# CON_PCIe_X4.net
KiCad netlist of a schematic drawn in Altium Designer
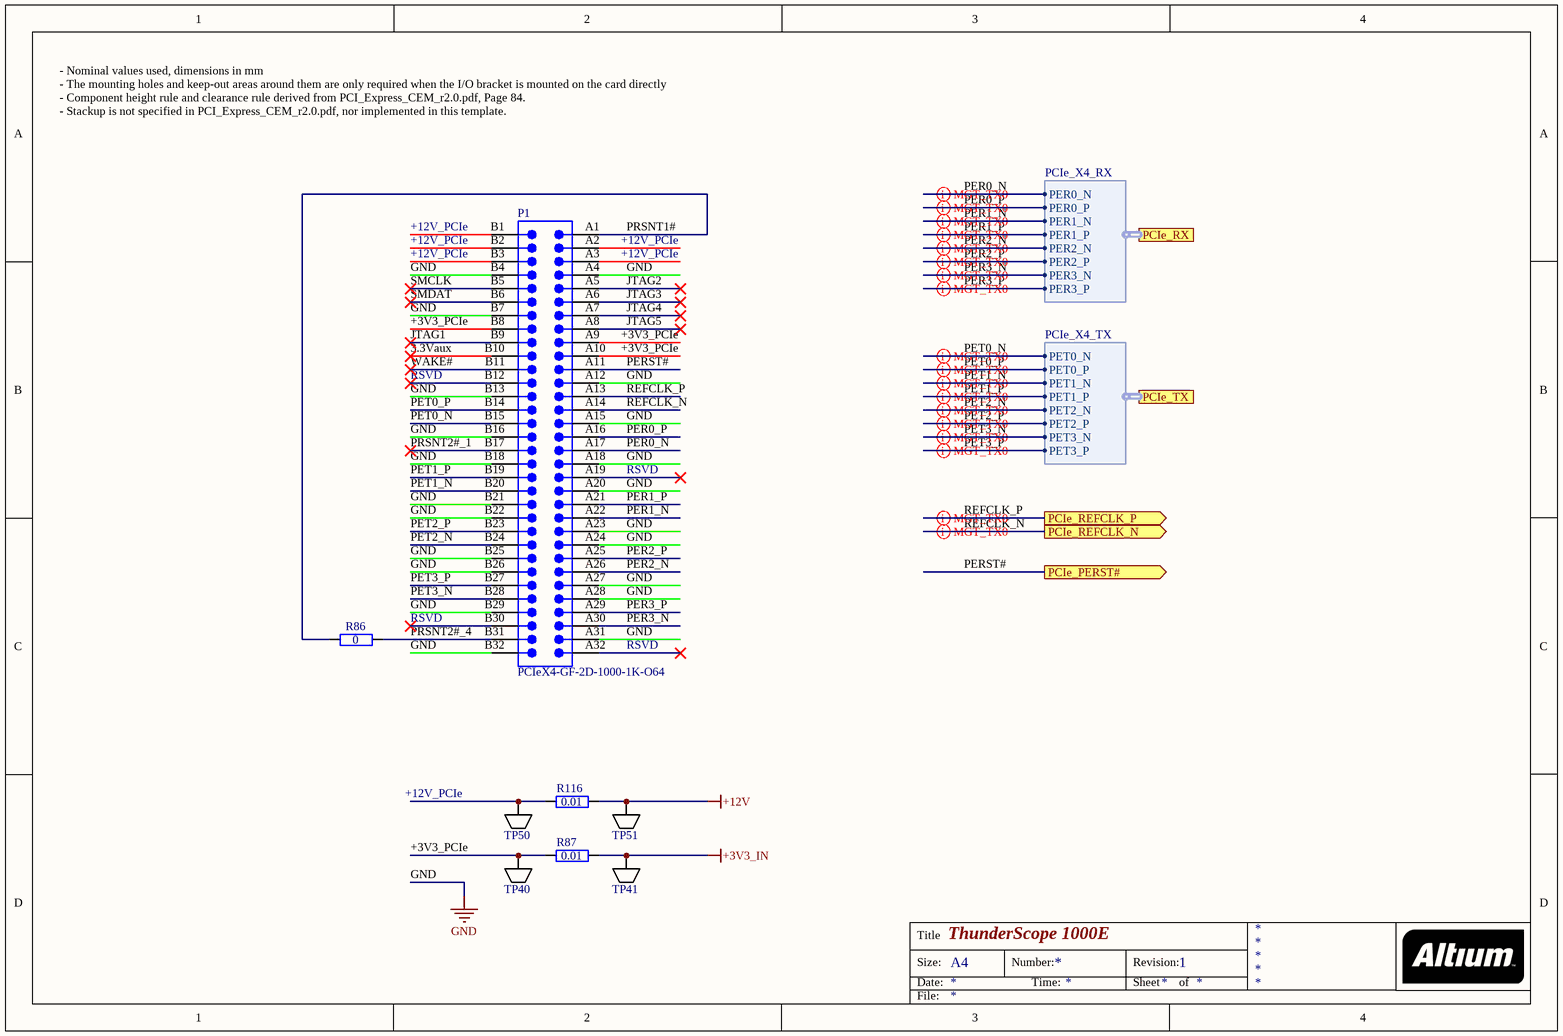
[diagram p0: CON_PCIe_X4.SchDoc]

(export (version "E")
  (design (tool "Eeschema 10.0.6"))
  (components
    (comp (ref "P1")
      (value "PCIeX4-GF-2D-1000-1K-O64")
      (footprint "PCIeX4-GF-2D-1000-1K-O64")
      (description "Golden finger, PCIeX4, Dual, Opposite, Pitch 1mm, 64-Position")
      (fields (field (name "PUBLISHER") "Altium"))
      (libsource (lib "Altium Content Vault") (part "PCIeX4-GF-2D-1000-1K-O64"))
    )
    (comp (ref "R86")
      (value "0")
      (footprint "GEN_R_0402")
      (libsource (lib "DSO") (part "RES 0 OHM 1/16W 0402"))
    )
    (comp (ref "R87")
      (value "0.01")
      (footprint "GEN_R_0603")
      (fields (field (name "TOLERANCE") "1%"))
      (libsource (lib "DSO") (part "RES 0.01 OHM 1% 1/4W 0603"))
    )
    (comp (ref "R116")
      (value "0.01")
      (footprint "GEN_R_0603")
      (fields (field (name "TOLERANCE") "1%"))
      (libsource (lib "DSO") (part "RES 0.01 OHM 1% 1/4W 0603"))
    )
    (comp (ref "TP40")
      (value "5015")
      (footprint "KEY_5015")
      (libsource (lib "DSO") (part "TP KEYSTONE 5015"))
    )
    (comp (ref "TP41")
      (value "5015")
      (footprint "KEY_5015")
      (libsource (lib "DSO") (part "TP KEYSTONE 5015"))
    )
    (comp (ref "TP50")
      (value "5015")
      (footprint "KEY_5015")
      (libsource (lib "DSO") (part "TP KEYSTONE 5015"))
    )
    (comp (ref "TP51")
      (value "5015")
      (footprint "KEY_5015")
      (libsource (lib "DSO") (part "TP KEYSTONE 5015"))
    )
  )
  (nets
    (net (code "3") (name "+3V3_IN") (class "Default")
      (node (ref "R87") (pin "2") (pinfunction "2_2") (pintype "passive"))
      (node (ref "TP41") (pin "1") (pinfunction "1_1") (pintype "passive"))
    )
    (net (code "4") (name "+12V") (class "Default")
      (node (ref "R116") (pin "2") (pinfunction "2_2") (pintype "passive"))
      (node (ref "TP51") (pin "1") (pinfunction "1_1") (pintype "passive"))
    )
    (net (code "5") (name "/+3V3_PCIe") (class "Default")
      (node (ref "P1") (pin "A10") (pinfunction "A10_A10") (pintype "passive"))
      (node (ref "P1") (pin "A9") (pinfunction "A9_A9") (pintype "passive"))
      (node (ref "P1") (pin "B8") (pinfunction "B8_B8") (pintype "passive"))
      (node (ref "R87") (pin "1") (pinfunction "1_1") (pintype "passive"))
      (node (ref "TP40") (pin "1") (pinfunction "1_1") (pintype "passive"))
    )
    (net (code "6") (name "/+12V_PCIe") (class "Default")
      (node (ref "P1") (pin "A2") (pinfunction "A2_A2") (pintype "passive"))
      (node (ref "P1") (pin "A3") (pinfunction "A3_A3") (pintype "passive"))
      (node (ref "P1") (pin "B1") (pinfunction "B1_B1") (pintype "passive"))
      (node (ref "P1") (pin "B2") (pinfunction "B2_B2") (pintype "passive"))
      (node (ref "P1") (pin "B3") (pinfunction "B3_B3") (pintype "passive"))
      (node (ref "R116") (pin "1") (pinfunction "1_1") (pintype "passive"))
      (node (ref "TP50") (pin "1") (pinfunction "1_1") (pintype "passive"))
    )
    (net (code "7") (name "/3.3Vaux") (class "Default")
      (node (ref "P1") (pin "B10") (pinfunction "B10_B10") (pintype "passive+no_connect"))
    )
    (net (code "8") (name "/JTAG1") (class "Default")
      (node (ref "P1") (pin "B9") (pinfunction "B9_B9") (pintype "passive+no_connect"))
    )
    (net (code "9") (name "/JTAG2") (class "Default")
      (node (ref "P1") (pin "A5") (pinfunction "A5_A5") (pintype "passive+no_connect"))
    )
    (net (code "10") (name "/JTAG3") (class "Default")
      (node (ref "P1") (pin "A6") (pinfunction "A6_A6") (pintype "passive+no_connect"))
    )
    (net (code "11") (name "/JTAG4") (class "Default")
      (node (ref "P1") (pin "A7") (pinfunction "A7_A7") (pintype "passive+no_connect"))
    )
    (net (code "12") (name "/JTAG5") (class "Default")
      (node (ref "P1") (pin "A8") (pinfunction "A8_A8") (pintype "passive+no_connect"))
    )
    (net (code "13") (name "/PER0_N") (class "Default")
      (node (ref "P1") (pin "A17") (pinfunction "A17_A17") (pintype "passive"))
    )
    (net (code "14") (name "/PER0_P") (class "Default")
      (node (ref "P1") (pin "A16") (pinfunction "A16_A16") (pintype "passive"))
    )
    (net (code "15") (name "/PER1_N") (class "Default")
      (node (ref "P1") (pin "A22") (pinfunction "A22_A22") (pintype "passive"))
    )
    (net (code "16") (name "/PER1_P") (class "Default")
      (node (ref "P1") (pin "A21") (pinfunction "A21_A21") (pintype "passive"))
    )
    (net (code "17") (name "/PER2_N") (class "Default")
      (node (ref "P1") (pin "A26") (pinfunction "A26_A26") (pintype "passive"))
    )
    (net (code "18") (name "/PER2_P") (class "Default")
      (node (ref "P1") (pin "A25") (pinfunction "A25_A25") (pintype "passive"))
    )
    (net (code "19") (name "/PER3_N") (class "Default")
      (node (ref "P1") (pin "A30") (pinfunction "A30_A30") (pintype "passive"))
    )
    (net (code "20") (name "/PER3_P") (class "Default")
      (node (ref "P1") (pin "A29") (pinfunction "A29_A29") (pintype "passive"))
    )
    (net (code "21") (name "/PERST#") (class "Default")
      (node (ref "P1") (pin "A11") (pinfunction "A11_A11") (pintype "passive"))
    )
    (net (code "22") (name "/PET0_N") (class "Default")
      (node (ref "P1") (pin "B15") (pinfunction "B15_B15") (pintype "passive"))
    )
    (net (code "23") (name "/PET0_P") (class "Default")
      (node (ref "P1") (pin "B14") (pinfunction "B14_B14") (pintype "passive"))
    )
    (net (code "24") (name "/PET1_N") (class "Default")
      (node (ref "P1") (pin "B20") (pinfunction "B20_B20") (pintype "passive"))
    )
    (net (code "25") (name "/PET1_P") (class "Default")
      (node (ref "P1") (pin "B19") (pinfunction "B19_B19") (pintype "passive"))
    )
    (net (code "26") (name "/PET2_N") (class "Default")
      (node (ref "P1") (pin "B24") (pinfunction "B24_B24") (pintype "passive"))
    )
    (net (code "27") (name "/PET2_P") (class "Default")
      (node (ref "P1") (pin "B23") (pinfunction "B23_B23") (pintype "passive"))
    )
    (net (code "28") (name "/PET3_N") (class "Default")
      (node (ref "P1") (pin "B28") (pinfunction "B28_B28") (pintype "passive"))
    )
    (net (code "29") (name "/PET3_P") (class "Default")
      (node (ref "P1") (pin "B27") (pinfunction "B27_B27") (pintype "passive"))
    )
    (net (code "30") (name "/PRSNT1#") (class "Default")
      (node (ref "P1") (pin "A1") (pinfunction "A1_A1") (pintype "passive"))
      (node (ref "R86") (pin "1") (pinfunction "1_1") (pintype "passive"))
    )
    (net (code "31") (name "/PRSNT2#_1") (class "Default")
      (node (ref "P1") (pin "B17") (pinfunction "B17_B17") (pintype "passive+no_connect"))
    )
    (net (code "32") (name "/PRSNT2#_4") (class "Default")
      (node (ref "P1") (pin "B31") (pinfunction "B31_B31") (pintype "passive"))
      (node (ref "R86") (pin "2") (pinfunction "2_2") (pintype "passive"))
    )
    (net (code "33") (name "/REFCLK_N") (class "Default")
      (node (ref "P1") (pin "A14") (pinfunction "A14_A14") (pintype "passive"))
    )
    (net (code "34") (name "/REFCLK_P") (class "Default")
      (node (ref "P1") (pin "A13") (pinfunction "A13_A13") (pintype "passive"))
    )
    (net (code "35") (name "/SMCLK") (class "Default")
      (node (ref "P1") (pin "B5") (pinfunction "B5_B5") (pintype "passive+no_connect"))
    )
    (net (code "36") (name "/SMDAT") (class "Default")
      (node (ref "P1") (pin "B6") (pinfunction "B6_B6") (pintype "passive+no_connect"))
    )
    (net (code "37") (name "/WAKE#") (class "Default")
      (node (ref "P1") (pin "B11") (pinfunction "B11_B11") (pintype "passive+no_connect"))
    )
    (net (code "40") (name "GND") (class "Default")
      (node (ref "P1") (pin "A12") (pinfunction "A12_A12") (pintype "passive"))
      (node (ref "P1") (pin "A15") (pinfunction "A15_A15") (pintype "passive"))
      (node (ref "P1") (pin "A18") (pinfunction "A18_A18") (pintype "passive"))
      (node (ref "P1") (pin "A20") (pinfunction "A20_A20") (pintype "passive"))
      (node (ref "P1") (pin "A23") (pinfunction "A23_A23") (pintype "passive"))
      (node (ref "P1") (pin "A24") (pinfunction "A24_A24") (pintype "passive"))
      (node (ref "P1") (pin "A27") (pinfunction "A27_A27") (pintype "passive"))
      (node (ref "P1") (pin "A28") (pinfunction "A28_A28") (pintype "passive"))
      (node (ref "P1") (pin "A31") (pinfunction "A31_A31") (pintype "passive"))
      (node (ref "P1") (pin "A4") (pinfunction "A4_A4") (pintype "passive"))
      (node (ref "P1") (pin "B13") (pinfunction "B13_B13") (pintype "passive"))
      (node (ref "P1") (pin "B16") (pinfunction "B16_B16") (pintype "passive"))
      (node (ref "P1") (pin "B18") (pinfunction "B18_B18") (pintype "passive"))
      (node (ref "P1") (pin "B21") (pinfunction "B21_B21") (pintype "passive"))
      (node (ref "P1") (pin "B22") (pinfunction "B22_B22") (pintype "passive"))
      (node (ref "P1") (pin "B25") (pinfunction "B25_B25") (pintype "passive"))
      (node (ref "P1") (pin "B26") (pinfunction "B26_B26") (pintype "passive"))
      (node (ref "P1") (pin "B29") (pinfunction "B29_B29") (pintype "passive"))
      (node (ref "P1") (pin "B32") (pinfunction "B32_B32") (pintype "passive"))
      (node (ref "P1") (pin "B4") (pinfunction "B4_B4") (pintype "passive"))
      (node (ref "P1") (pin "B7") (pinfunction "B7_B7") (pintype "passive"))
    )
    (net (code "41") (name "unconnected-(P1-PadA19)") (class "Default")
      (node (ref "P1") (pin "A19") (pinfunction "A19_A19") (pintype "passive+no_connect"))
    )
    (net (code "42") (name "unconnected-(P1-PadA32)") (class "Default")
      (node (ref "P1") (pin "A32") (pinfunction "A32_A32") (pintype "passive+no_connect"))
    )
    (net (code "43") (name "unconnected-(P1-PadB12)") (class "Default")
      (node (ref "P1") (pin "B12") (pinfunction "B12_B12") (pintype "passive+no_connect"))
    )
    (net (code "44") (name "unconnected-(P1-PadB30)") (class "Default")
      (node (ref "P1") (pin "B30") (pinfunction "B30_B30") (pintype "passive+no_connect"))
    )
  )
)
